# amplifier.net
KiCad netlist of a schematic drawn in EAGLE
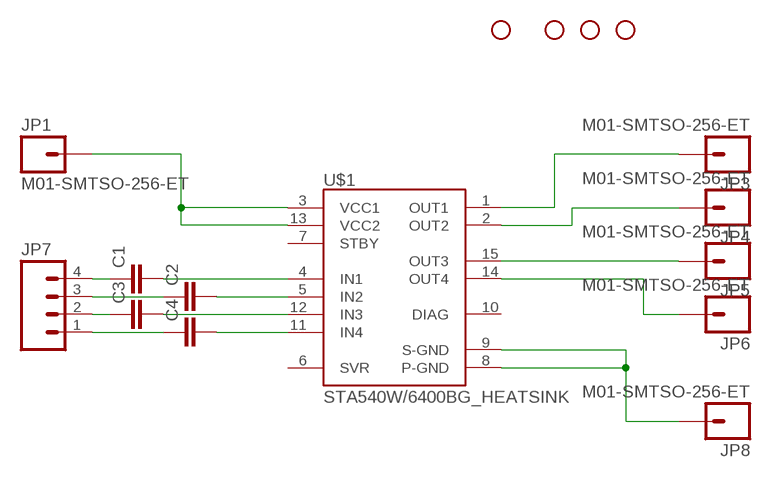
[diagram p0: schematic, sheet 1]

(export (version "E")
  (design (tool "Eeschema 10.0.6"))
  (components
    (comp (ref "C1")
      (value "CAP1206")
      (footprint "eagle-import:1206")
      (libsource (lib "eagle-import") (part "CAP1206"))
    )
    (comp (ref "C2")
      (value "CAP1206")
      (footprint "eagle-import:1206")
      (libsource (lib "eagle-import") (part "CAP1206"))
    )
    (comp (ref "C3")
      (value "CAP1206")
      (footprint "eagle-import:1206")
      (libsource (lib "eagle-import") (part "CAP1206"))
    )
    (comp (ref "C4")
      (value "CAP1206")
      (footprint "eagle-import:1206")
      (libsource (lib "eagle-import") (part "CAP1206"))
    )
    (comp (ref "JP1")
      (value "M01-SMTSO-256-ET")
      (footprint "eagle-import:SMTSO-256-ET")
      (libsource (lib "eagle-import") (part "M01-SMTSO-256-ET"))
    )
    (comp (ref "JP3")
      (value "M01-SMTSO-256-ET")
      (footprint "eagle-import:SMTSO-256-ET")
      (libsource (lib "eagle-import") (part "M01-SMTSO-256-ET"))
    )
    (comp (ref "JP4")
      (value "M01-SMTSO-256-ET")
      (footprint "eagle-import:SMTSO-256-ET")
      (libsource (lib "eagle-import") (part "M01-SMTSO-256-ET"))
    )
    (comp (ref "JP5")
      (value "M01-SMTSO-256-ET")
      (footprint "eagle-import:SMTSO-256-ET")
      (libsource (lib "eagle-import") (part "M01-SMTSO-256-ET"))
    )
    (comp (ref "JP6")
      (value "M01-SMTSO-256-ET")
      (footprint "eagle-import:SMTSO-256-ET")
      (libsource (lib "eagle-import") (part "M01-SMTSO-256-ET"))
    )
    (comp (ref "JP7")
      (value "M04PTH")
      (footprint "eagle-import:1X04")
      (libsource (lib "eagle-import") (part "M04PTH"))
    )
    (comp (ref "JP8")
      (value "M01-SMTSO-256-ET")
      (footprint "eagle-import:SMTSO-256-ET")
      (libsource (lib "eagle-import") (part "M01-SMTSO-256-ET"))
    )
    (comp (ref "STANDOFF1")
      (value "STAND-OFF")
      (footprint "eagle-import:STAND-OFF")
      (libsource (lib "eagle-import") (part "STAND-OFF"))
    )
    (comp (ref "STANDOFF2")
      (value "STAND-OFF")
      (footprint "eagle-import:STAND-OFF")
      (libsource (lib "eagle-import") (part "STAND-OFF"))
    )
    (comp (ref "STANDOFF3")
      (value "STAND-OFF")
      (footprint "eagle-import:STAND-OFF")
      (libsource (lib "eagle-import") (part "STAND-OFF"))
    )
    (comp (ref "STANDOFF4")
      (value "STAND-OFF")
      (footprint "eagle-import:STAND-OFF")
      (libsource (lib "eagle-import") (part "STAND-OFF"))
    )
    (comp (ref "U$1")
      (value "STA540W/6400BG_HEATSINK")
      (footprint "eagle-import:MULTIWATT15_6400BGHEATSINK")
      (libsource (lib "eagle-import") (part "STA540W/6400BG_HEATSINK"))
    )
  )
  (nets
    (net (code "1") (name "Net-(C1-Pad1)") (class "Default")
      (node (ref "C1") (pin "1") (pinfunction "1_1") (pintype "passive"))
      (node (ref "JP7") (pin "4") (pinfunction "4_4") (pintype "passive"))
    )
    (net (code "2") (name "Net-(C2-Pad1)") (class "Default")
      (node (ref "C2") (pin "1") (pinfunction "1_1") (pintype "passive"))
      (node (ref "JP7") (pin "3") (pinfunction "3_3") (pintype "passive"))
    )
    (net (code "3") (name "Net-(C3-Pad1)") (class "Default")
      (node (ref "C3") (pin "1") (pinfunction "1_1") (pintype "passive"))
      (node (ref "JP7") (pin "2") (pinfunction "2_2") (pintype "passive"))
    )
    (net (code "4") (name "Net-(C4-Pad1)") (class "Default")
      (node (ref "C4") (pin "1") (pinfunction "1_1") (pintype "passive"))
      (node (ref "JP7") (pin "1") (pinfunction "1_1") (pintype "passive"))
    )
    (net (code "5") (name "Net-(JP1-1)") (class "Default")
      (node (ref "JP1") (pin "P$1") (pinfunction "1_P$1") (pintype "passive"))
      (node (ref "U$1") (pin "13") (pinfunction "VCC2_13") (pintype "bidirectional"))
      (node (ref "U$1") (pin "3") (pinfunction "VCC1_3") (pintype "bidirectional"))
    )
    (net (code "6") (name "Net-(JP3-1)") (class "Default")
      (node (ref "JP3") (pin "P$1") (pinfunction "1_P$1") (pintype "passive"))
      (node (ref "U$1") (pin "1") (pinfunction "OUT1_1") (pintype "bidirectional"))
    )
    (net (code "7") (name "Net-(JP4-1)") (class "Default")
      (node (ref "JP4") (pin "P$1") (pinfunction "1_P$1") (pintype "passive"))
      (node (ref "U$1") (pin "2") (pinfunction "OUT2_2") (pintype "bidirectional"))
    )
    (net (code "8") (name "Net-(JP5-1)") (class "Default")
      (node (ref "JP5") (pin "P$1") (pinfunction "1_P$1") (pintype "passive"))
      (node (ref "U$1") (pin "15") (pinfunction "OUT3_15") (pintype "bidirectional"))
    )
    (net (code "9") (name "Net-(JP6-1)") (class "Default")
      (node (ref "JP6") (pin "P$1") (pinfunction "1_P$1") (pintype "passive"))
      (node (ref "U$1") (pin "14") (pinfunction "OUT4_14") (pintype "bidirectional"))
    )
    (net (code "10") (name "Net-(JP8-1)") (class "Default")
      (node (ref "JP8") (pin "P$1") (pinfunction "1_P$1") (pintype "passive"))
      (node (ref "U$1") (pin "8") (pinfunction "P-GND_8") (pintype "bidirectional"))
      (node (ref "U$1") (pin "9") (pinfunction "S-GND_9") (pintype "bidirectional"))
    )
    (net (code "11") (name "Net-(U$1-IN1)") (class "Default")
      (node (ref "C1") (pin "2") (pinfunction "2_2") (pintype "passive"))
      (node (ref "U$1") (pin "4") (pinfunction "IN1_4") (pintype "bidirectional"))
    )
    (net (code "12") (name "Net-(U$1-IN2)") (class "Default")
      (node (ref "C2") (pin "2") (pinfunction "2_2") (pintype "passive"))
      (node (ref "U$1") (pin "5") (pinfunction "IN2_5") (pintype "bidirectional"))
    )
    (net (code "13") (name "Net-(U$1-IN3)") (class "Default")
      (node (ref "C3") (pin "2") (pinfunction "2_2") (pintype "passive"))
      (node (ref "U$1") (pin "12") (pinfunction "IN3_12") (pintype "bidirectional"))
    )
    (net (code "14") (name "Net-(U$1-IN4)") (class "Default")
      (node (ref "C4") (pin "2") (pinfunction "2_2") (pintype "passive"))
      (node (ref "U$1") (pin "11") (pinfunction "IN4_11") (pintype "bidirectional"))
    )
    (net (code "15") (name "unconnected-(U$1-DIAG-Pad10)") (class "Default")
      (node (ref "U$1") (pin "10") (pinfunction "DIAG_10") (pintype "bidirectional"))
    )
    (net (code "16") (name "unconnected-(U$1-STBY-Pad7)") (class "Default")
      (node (ref "U$1") (pin "7") (pinfunction "STBY_7") (pintype "bidirectional"))
    )
    (net (code "17") (name "unconnected-(U$1-SVR-Pad6)") (class "Default")
      (node (ref "U$1") (pin "6") (pinfunction "SVR_6") (pintype "bidirectional"))
    )
  )
)
